# General_Overview.net
KiCad netlist of a schematic drawn in Altium Designer
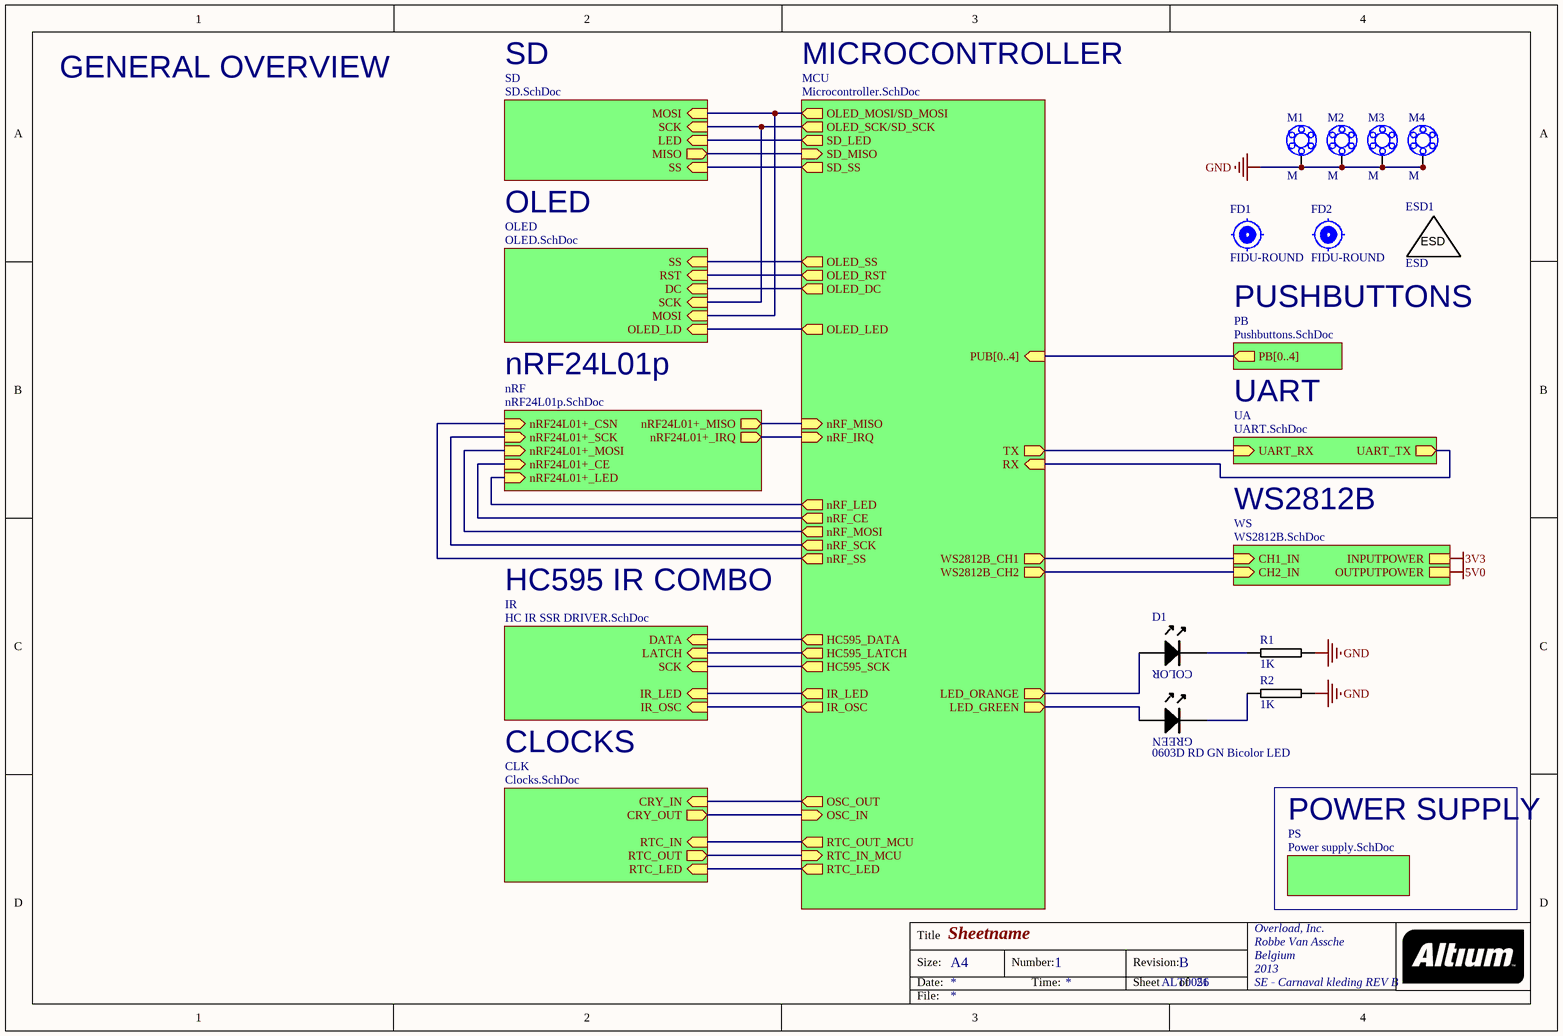
[diagram p0: General Overview.SchDoc]

(export (version "E")
  (design (tool "Eeschema 10.0.6"))
  (components
    (comp (ref "D1")
      (value "0603D RD GN Bicolor LED")
      (footprint "0606LED BiCOLOR")
      (description "Bicolor 0603 LED")
      (libsource (lib "RVA_LED_SMD_0603") (part "0603D RD GN Bicolor LED"))
    )
    (comp (ref "ESD1")
      (value "ESD")
      (footprint "ESDSILK")
      (description "ESD LOGO")
      (libsource (lib "vh_altium_library") (part "ESD"))
    )
    (comp (ref "FD1")
      (value "FIDU-ROUND")
      (footprint "FIDU-ROUND")
      (description "ROUND FIDUCIAL")
      (libsource (lib "vh_altium_library") (part "FIDU-ROUND"))
    )
    (comp (ref "FD2")
      (value "FIDU-ROUND")
      (footprint "FIDU-ROUND")
      (description "ROUND FIDUCIAL")
      (libsource (lib "vh_altium_library") (part "FIDU-ROUND"))
    )
    (comp (ref "M1")
      (value "M")
      (footprint "MOUNTING")
      (description "MOUNTING HOLE - NON INSTALLABLE")
      (libsource (lib "vh_altium_library") (part "MOUNTING"))
    )
    (comp (ref "M2")
      (value "M")
      (footprint "MOUNTING")
      (description "MOUNTING HOLE - NON INSTALLABLE")
      (libsource (lib "vh_altium_library") (part "MOUNTING"))
    )
    (comp (ref "M3")
      (value "M")
      (footprint "MOUNTING")
      (description "MOUNTING HOLE - NON INSTALLABLE")
      (libsource (lib "vh_altium_library") (part "MOUNTING"))
    )
    (comp (ref "M4")
      (value "M")
      (footprint "MOUNTING")
      (description "MOUNTING HOLE - NON INSTALLABLE")
      (libsource (lib "vh_altium_library") (part "MOUNTING"))
    )
    (comp (ref "R1")
      (value "1K")
      (footprint "0603R-1k")
      (description "GENERIC RESISTOR 0603")
      (fields
        (field (name "MANUFACTURER PART NUMBER") "RMCF 1/16 1K 1% R")
        (field (name "MANUFACTURER") "Stackpole Electronics Inc")
      )
      (libsource (lib "RVA_Altium_Library") (part "0603R-1K"))
    )
    (comp (ref "R2")
      (value "1K")
      (footprint "0603R-1k")
      (description "GENERIC RESISTOR 0603")
      (fields
        (field (name "MANUFACTURER PART NUMBER") "RMCF 1/16 1K 1% R")
        (field (name "MANUFACTURER") "Stackpole Electronics Inc")
      )
      (libsource (lib "RVA_Altium_Library") (part "0603R-1K"))
    )
  )
  (nets
    (net (code "7") (name "/LED_GREEN") (class "Default") (node (ref "D1") (pin "A1") (pintype "passive")))
    (net (code "8") (name "/LED_ORANGE") (class "Default") (node (ref "D1") (pin "A2") (pintype "passive")))
    (net (code "36") (name "GND") (class "Default")
      (node (ref "M1") (pin "1") (pinfunction "1_1") (pintype "passive"))
      (node (ref "M1") (pin "2") (pinfunction "2_2") (pintype "passive"))
      (node (ref "M1") (pin "3") (pinfunction "3_3") (pintype "passive"))
      (node (ref "M1") (pin "4") (pinfunction "4_4") (pintype "passive"))
      (node (ref "M1") (pin "5") (pinfunction "5_5") (pintype "passive"))
      (node (ref "M1") (pin "6") (pinfunction "6_6") (pintype "passive"))
      (node (ref "M1") (pin "7") (pinfunction "7_7") (pintype "passive"))
      (node (ref "M2") (pin "1") (pinfunction "1_1") (pintype "passive"))
      (node (ref "M2") (pin "2") (pinfunction "2_2") (pintype "passive"))
      (node (ref "M2") (pin "3") (pinfunction "3_3") (pintype "passive"))
      (node (ref "M2") (pin "4") (pinfunction "4_4") (pintype "passive"))
      (node (ref "M2") (pin "5") (pinfunction "5_5") (pintype "passive"))
      (node (ref "M2") (pin "6") (pinfunction "6_6") (pintype "passive"))
      (node (ref "M2") (pin "7") (pinfunction "7_7") (pintype "passive"))
      (node (ref "M3") (pin "1") (pinfunction "1_1") (pintype "passive"))
      (node (ref "M3") (pin "2") (pinfunction "2_2") (pintype "passive"))
      (node (ref "M3") (pin "3") (pinfunction "3_3") (pintype "passive"))
      (node (ref "M3") (pin "4") (pinfunction "4_4") (pintype "passive"))
      (node (ref "M3") (pin "5") (pinfunction "5_5") (pintype "passive"))
      (node (ref "M3") (pin "6") (pinfunction "6_6") (pintype "passive"))
      (node (ref "M3") (pin "7") (pinfunction "7_7") (pintype "passive"))
      (node (ref "M4") (pin "1") (pinfunction "1_1") (pintype "passive"))
      (node (ref "M4") (pin "2") (pinfunction "2_2") (pintype "passive"))
      (node (ref "M4") (pin "3") (pinfunction "3_3") (pintype "passive"))
      (node (ref "M4") (pin "4") (pinfunction "4_4") (pintype "passive"))
      (node (ref "M4") (pin "5") (pinfunction "5_5") (pintype "passive"))
      (node (ref "M4") (pin "6") (pinfunction "6_6") (pintype "passive"))
      (node (ref "M4") (pin "7") (pinfunction "7_7") (pintype "passive"))
      (node (ref "R1") (pin "2") (pintype "passive"))
      (node (ref "R2") (pin "2") (pintype "passive"))
    )
    (net (code "37") (name "Net-(D1-PadK1)") (class "Default")
      (node (ref "D1") (pin "K1") (pintype "passive"))
      (node (ref "R2") (pin "1") (pintype "passive"))
    )
    (net (code "38") (name "Net-(D1-PadK2)") (class "Default")
      (node (ref "D1") (pin "K2") (pintype "passive"))
      (node (ref "R1") (pin "1") (pintype "passive"))
    )
  )
)
